# usb-pedal.net
KiCad netlist of a schematic drawn in EAGLE
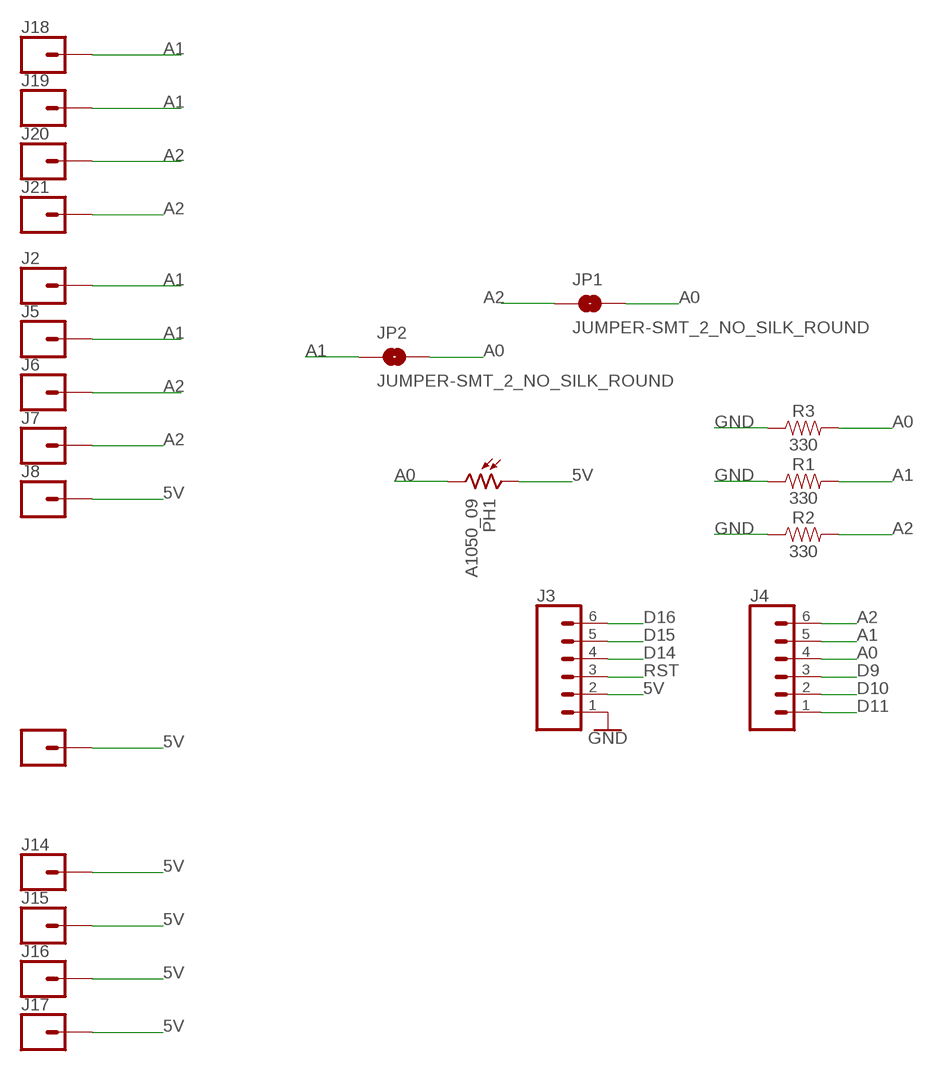
[diagram p0: schematic, sheet 1]

(export (version "E")
  (design (tool "Eeschema 10.0.6"))
  (components
    (comp (ref "J2")
      (value "CONN_01SMTSO-256-ET-0.165DIA")
      (footprint "eagle-import:SMTSO-256-ET-0.165DIA")
      (libsource (lib "eagle-import") (part "CONN_01SMTSO-256-ET-0.165DIA"))
    )
    (comp (ref "J3")
      (value "CONN_06LOCK")
      (footprint "eagle-import:1X06_LOCK")
      (libsource (lib "eagle-import") (part "CONN_06LOCK"))
    )
    (comp (ref "J4")
      (value "CONN_06LOCK")
      (footprint "eagle-import:1X06_LOCK")
      (libsource (lib "eagle-import") (part "CONN_06LOCK"))
    )
    (comp (ref "J5")
      (value "CONN_01SMTSO-256-ET-0.165DIA")
      (footprint "eagle-import:SMTSO-256-ET-0.165DIA")
      (libsource (lib "eagle-import") (part "CONN_01SMTSO-256-ET-0.165DIA"))
    )
    (comp (ref "J6")
      (value "CONN_01SMTSO-256-ET-0.165DIA")
      (footprint "eagle-import:SMTSO-256-ET-0.165DIA")
      (libsource (lib "eagle-import") (part "CONN_01SMTSO-256-ET-0.165DIA"))
    )
    (comp (ref "J7")
      (value "CONN_01SMTSO-256-ET-0.165DIA")
      (footprint "eagle-import:SMTSO-256-ET-0.165DIA")
      (libsource (lib "eagle-import") (part "CONN_01SMTSO-256-ET-0.165DIA"))
    )
    (comp (ref "J8")
      (value "CONN_01SMTSO-256-ET-0.165DIA")
      (footprint "eagle-import:SMTSO-256-ET-0.165DIA")
      (libsource (lib "eagle-import") (part "CONN_01SMTSO-256-ET-0.165DIA"))
    )
    (comp (ref "J12")
      (value "CONN_01SMTSO-256-ET-0.165DIA")
      (footprint "eagle-import:SMTSO-256-ET-0.165DIA")
      (libsource (lib "eagle-import") (part "CONN_01SMTSO-256-ET-0.165DIA"))
    )
    (comp (ref "J14")
      (value "CONN_01SMTSO-256-ET-0.165DIA")
      (footprint "eagle-import:SMTSO-256-ET-0.165DIA")
      (libsource (lib "eagle-import") (part "CONN_01SMTSO-256-ET-0.165DIA"))
    )
    (comp (ref "J15")
      (value "CONN_01SMTSO-256-ET-0.165DIA")
      (footprint "eagle-import:SMTSO-256-ET-0.165DIA")
      (libsource (lib "eagle-import") (part "CONN_01SMTSO-256-ET-0.165DIA"))
    )
    (comp (ref "J16")
      (value "CONN_01SMTSO-256-ET-0.165DIA")
      (footprint "eagle-import:SMTSO-256-ET-0.165DIA")
      (libsource (lib "eagle-import") (part "CONN_01SMTSO-256-ET-0.165DIA"))
    )
    (comp (ref "J17")
      (value "CONN_01SMTSO-256-ET-0.165DIA")
      (footprint "eagle-import:SMTSO-256-ET-0.165DIA")
      (libsource (lib "eagle-import") (part "CONN_01SMTSO-256-ET-0.165DIA"))
    )
    (comp (ref "J18")
      (value "CONN_01SMTSO-256-ET-0.165DIA")
      (footprint "eagle-import:SMTSO-256-ET-0.165DIA")
      (libsource (lib "eagle-import") (part "CONN_01SMTSO-256-ET-0.165DIA"))
    )
    (comp (ref "J19")
      (value "CONN_01SMTSO-256-ET-0.165DIA")
      (footprint "eagle-import:SMTSO-256-ET-0.165DIA")
      (libsource (lib "eagle-import") (part "CONN_01SMTSO-256-ET-0.165DIA"))
    )
    (comp (ref "J20")
      (value "CONN_01SMTSO-256-ET-0.165DIA")
      (footprint "eagle-import:SMTSO-256-ET-0.165DIA")
      (libsource (lib "eagle-import") (part "CONN_01SMTSO-256-ET-0.165DIA"))
    )
    (comp (ref "J21")
      (value "CONN_01SMTSO-256-ET-0.165DIA")
      (footprint "eagle-import:SMTSO-256-ET-0.165DIA")
      (libsource (lib "eagle-import") (part "CONN_01SMTSO-256-ET-0.165DIA"))
    )
    (comp (ref "JP1")
      (value "JUMPER-SMT_2_NO_SILK_ROUND")
      (footprint "eagle-import:SMT-JUMPER_2_NO_SILK_ROUND")
      (libsource (lib "eagle-import") (part "JUMPER-SMT_2_NO_SILK_ROUND"))
    )
    (comp (ref "JP2")
      (value "JUMPER-SMT_2_NO_SILK_ROUND")
      (footprint "eagle-import:SMT-JUMPER_2_NO_SILK_ROUND")
      (libsource (lib "eagle-import") (part "JUMPER-SMT_2_NO_SILK_ROUND"))
    )
    (comp (ref "PH1")
      (value "A1050_09")
      (footprint "eagle-import:T0-46-A10XX")
      (libsource (lib "eagle-import") (part "A1050_09"))
    )
    (comp (ref "R1")
      (value "330")
      (footprint "eagle-import:AXIAL-0.3")
      (libsource (lib "eagle-import") (part "330OHM-HORIZ-1/10W-5%"))
    )
    (comp (ref "R2")
      (value "330")
      (footprint "eagle-import:AXIAL-0.3")
      (libsource (lib "eagle-import") (part "330OHM-HORIZ-1/10W-5%"))
    )
    (comp (ref "R3")
      (value "330")
      (footprint "eagle-import:AXIAL-0.3")
      (libsource (lib "eagle-import") (part "330OHM-HORIZ-1/10W-5%"))
    )
  )
  (nets
    (net (code "1") (name "/5V") (class "Default")
      (node (ref "J12") (pin "P$1") (pinfunction "1_P$1") (pintype "passive"))
      (node (ref "J14") (pin "P$1") (pinfunction "1_P$1") (pintype "passive"))
      (node (ref "J15") (pin "P$1") (pinfunction "1_P$1") (pintype "passive"))
      (node (ref "J16") (pin "P$1") (pinfunction "1_P$1") (pintype "passive"))
      (node (ref "J17") (pin "P$1") (pinfunction "1_P$1") (pintype "passive"))
      (node (ref "J3") (pin "2") (pinfunction "2_2") (pintype "passive"))
      (node (ref "J8") (pin "P$1") (pinfunction "1_P$1") (pintype "passive"))
      (node (ref "PH1") (pin "1") (pinfunction "1_1") (pintype "passive"))
    )
    (net (code "2") (name "/A0") (class "Default")
      (node (ref "J4") (pin "4") (pinfunction "4_4") (pintype "passive"))
      (node (ref "JP1") (pin "2") (pinfunction "2_2") (pintype "passive"))
      (node (ref "JP2") (pin "2") (pinfunction "2_2") (pintype "passive"))
      (node (ref "PH1") (pin "2") (pinfunction "2_2") (pintype "passive"))
      (node (ref "R3") (pin "P$2") (pinfunction "2_P$2") (pintype "passive"))
    )
    (net (code "3") (name "/A1") (class "Default")
      (node (ref "J18") (pin "P$1") (pinfunction "1_P$1") (pintype "passive"))
      (node (ref "J19") (pin "P$1") (pinfunction "1_P$1") (pintype "passive"))
      (node (ref "J2") (pin "P$1") (pinfunction "1_P$1") (pintype "passive"))
      (node (ref "J4") (pin "5") (pinfunction "5_5") (pintype "passive"))
      (node (ref "J5") (pin "P$1") (pinfunction "1_P$1") (pintype "passive"))
      (node (ref "JP2") (pin "1") (pinfunction "1_1") (pintype "passive"))
      (node (ref "R1") (pin "P$2") (pinfunction "2_P$2") (pintype "passive"))
    )
    (net (code "4") (name "/A2") (class "Default")
      (node (ref "J20") (pin "P$1") (pinfunction "1_P$1") (pintype "passive"))
      (node (ref "J21") (pin "P$1") (pinfunction "1_P$1") (pintype "passive"))
      (node (ref "J4") (pin "6") (pinfunction "6_6") (pintype "passive"))
      (node (ref "J6") (pin "P$1") (pinfunction "1_P$1") (pintype "passive"))
      (node (ref "J7") (pin "P$1") (pinfunction "1_P$1") (pintype "passive"))
      (node (ref "JP1") (pin "1") (pinfunction "1_1") (pintype "passive"))
      (node (ref "R2") (pin "P$2") (pinfunction "2_P$2") (pintype "passive"))
    )
    (net (code "5") (name "/D9") (class "Default")
      (node (ref "J4") (pin "3") (pinfunction "3_3") (pintype "passive"))
    )
    (net (code "6") (name "/D10") (class "Default")
      (node (ref "J4") (pin "2") (pinfunction "2_2") (pintype "passive"))
    )
    (net (code "7") (name "/D11") (class "Default")
      (node (ref "J4") (pin "1") (pinfunction "1_1") (pintype "passive"))
    )
    (net (code "8") (name "/D14") (class "Default")
      (node (ref "J3") (pin "4") (pinfunction "4_4") (pintype "passive"))
    )
    (net (code "9") (name "/D15") (class "Default")
      (node (ref "J3") (pin "5") (pinfunction "5_5") (pintype "passive"))
    )
    (net (code "10") (name "/D16") (class "Default")
      (node (ref "J3") (pin "6") (pinfunction "6_6") (pintype "passive"))
    )
    (net (code "11") (name "/RST") (class "Default")
      (node (ref "J3") (pin "3") (pinfunction "3_3") (pintype "passive"))
    )
    (net (code "12") (name "GND") (class "Default")
      (node (ref "J3") (pin "1") (pinfunction "1_1") (pintype "passive"))
      (node (ref "R1") (pin "P$1") (pinfunction "1_P$1") (pintype "passive"))
      (node (ref "R2") (pin "P$1") (pinfunction "1_P$1") (pintype "passive"))
      (node (ref "R3") (pin "P$1") (pinfunction "1_P$1") (pintype "passive"))
    )
  )
)
